# CS_NAV_SNS.net
KiCad netlist of a schematic drawn in EAGLE
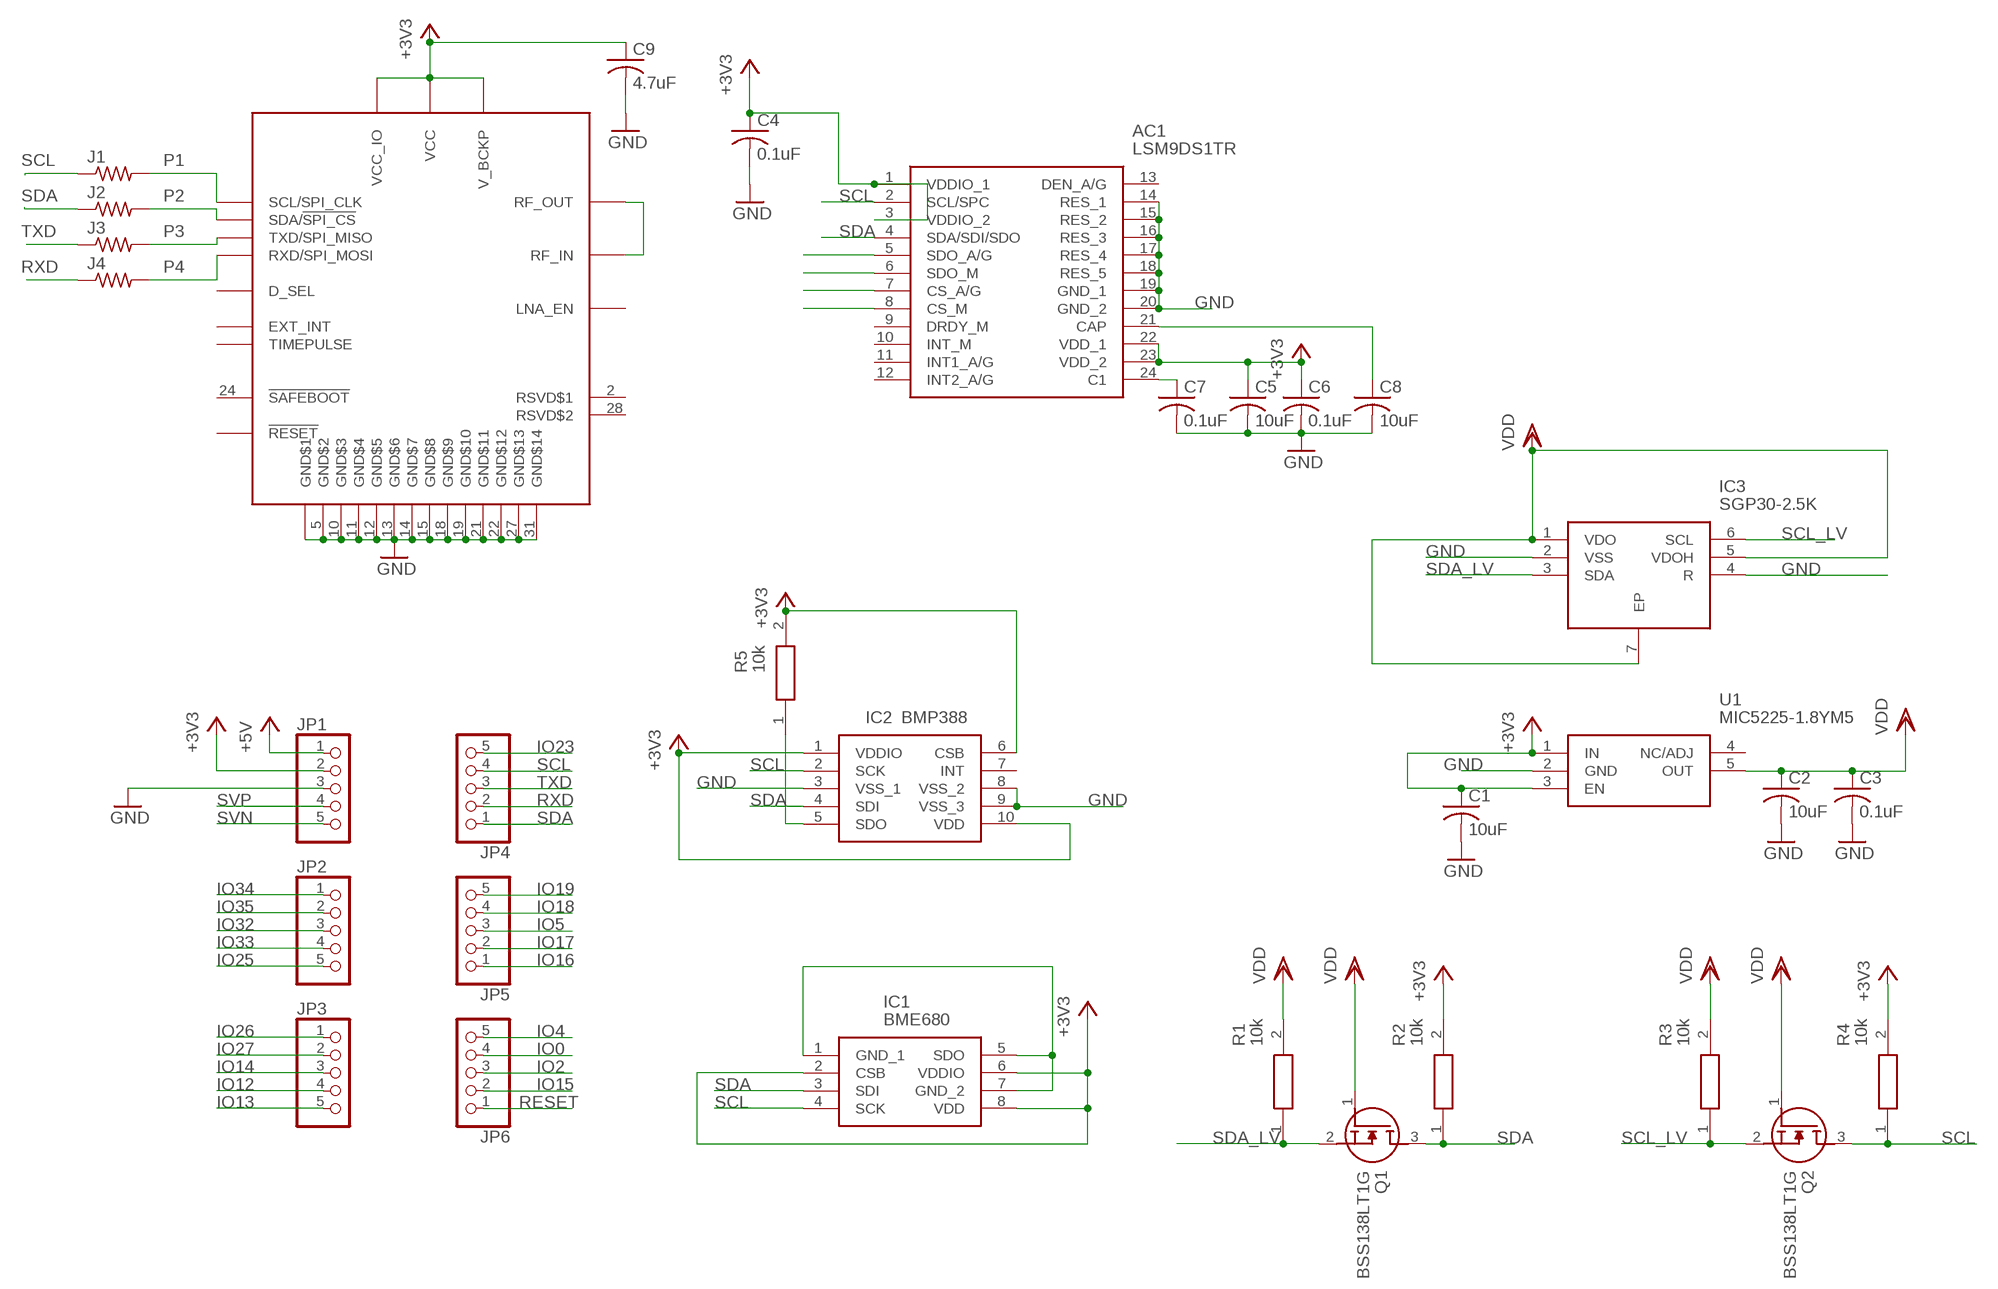
[diagram p0: schematic, sheet 1]

(export (version "E")
  (design (tool "Eeschema 10.0.6"))
  (components
    (comp (ref "AC1")
      (value "LSM9DS1TR")
      (footprint "eagle-import:LGA-24L(3X3.5X1MM)")
      (fields (field (name "MOUSER_PART_NUMBER") "511-LSM9DS1TR") (field (name "RS_PART_NUMBER") "1660908"))
      (libsource (lib "eagle-import") (part "LSM9DS1TR"))
    )
    (comp (ref "C1")
      (value "10uF")
      (footprint "eagle-import:C0805")
      (libsource (lib "eagle-import") (part "C-USC0805"))
    )
    (comp (ref "C2")
      (value "10uF")
      (footprint "eagle-import:C0805")
      (libsource (lib "eagle-import") (part "C-USC0805"))
    )
    (comp (ref "C3")
      (value "0.1uF")
      (footprint "eagle-import:C0805")
      (libsource (lib "eagle-import") (part "C-USC0805"))
    )
    (comp (ref "C4")
      (value "0.1uF")
      (footprint "eagle-import:C0805")
      (libsource (lib "eagle-import") (part "C-USC0805"))
    )
    (comp (ref "C5")
      (value "10uF")
      (footprint "eagle-import:C0805")
      (libsource (lib "eagle-import") (part "C-USC0805"))
    )
    (comp (ref "C6")
      (value "0.1uF")
      (footprint "eagle-import:C0805")
      (libsource (lib "eagle-import") (part "C-USC0805"))
    )
    (comp (ref "C7")
      (value "0.1uF")
      (footprint "eagle-import:C0805")
      (libsource (lib "eagle-import") (part "C-USC0805"))
    )
    (comp (ref "C8")
      (value "10uF")
      (footprint "eagle-import:C0805")
      (libsource (lib "eagle-import") (part "C-USC0805"))
    )
    (comp (ref "C9")
      (value "4.7uF")
      (footprint "eagle-import:C0805")
      (libsource (lib "eagle-import") (part "C-USC0805"))
    )
    (comp (ref "IC1")
      (value "BME680")
      (footprint "eagle-import:BME680")
      (fields (field (name "MOUSER_PART_NUMBER") "262-BME680"))
      (libsource (lib "eagle-import") (part "BME680"))
    )
    (comp (ref "IC2")
      (value "BMP388")
      (footprint "eagle-import:BMP388")
      (fields (field (name "MOUSER_PART_NUMBER") "262-BMP388"))
      (libsource (lib "eagle-import") (part "BMP388"))
    )
    (comp (ref "IC3")
      (value "SGP30-2.5K")
      (footprint "eagle-import:SON80P245X245X90-7N")
      (fields
        (field (name "MANUFACTURER_PART_NUMBER") "SGP30-2.5k")
        (field (name "MOUSER_PART_NUMBER") "403-SGP30-2.5K")
        (field (name "RS_PART_NUMBER") "1463573")
      )
      (libsource (lib "eagle-import") (part "SGP30-2.5K"))
    )
    (comp (ref "J1")
      (value "R-US_R1206")
      (footprint "eagle-import:R1206")
      (libsource (lib "eagle-import") (part "R-US_R1206"))
    )
    (comp (ref "J2")
      (value "R-US_R1206")
      (footprint "eagle-import:R1206")
      (libsource (lib "eagle-import") (part "R-US_R1206"))
    )
    (comp (ref "J3")
      (value "R-US_R1206")
      (footprint "eagle-import:R1206")
      (libsource (lib "eagle-import") (part "R-US_R1206"))
    )
    (comp (ref "J4")
      (value "R-US_R1206")
      (footprint "eagle-import:R1206")
      (libsource (lib "eagle-import") (part "R-US_R1206"))
    )
    (comp (ref "JP1")
      (value "PINHD-1X5")
      (footprint "eagle-import:1X05")
      (libsource (lib "eagle-import") (part "PINHD-1X5"))
    )
    (comp (ref "JP2")
      (value "PINHD-1X5")
      (footprint "eagle-import:1X05")
      (libsource (lib "eagle-import") (part "PINHD-1X5"))
    )
    (comp (ref "JP3")
      (value "PINHD-1X5")
      (footprint "eagle-import:1X05")
      (libsource (lib "eagle-import") (part "PINHD-1X5"))
    )
    (comp (ref "JP4")
      (value "PINHD-1X5")
      (footprint "eagle-import:1X05")
      (libsource (lib "eagle-import") (part "PINHD-1X5"))
    )
    (comp (ref "JP5")
      (value "PINHD-1X5")
      (footprint "eagle-import:1X05")
      (libsource (lib "eagle-import") (part "PINHD-1X5"))
    )
    (comp (ref "JP6")
      (value "PINHD-1X5")
      (footprint "eagle-import:1X05")
      (libsource (lib "eagle-import") (part "PINHD-1X5"))
    )
    (comp (ref "Q1")
      (value "BSS138LT1G")
      (footprint "eagle-import:SOT96P237X111-3N")
      (fields (field (name "MOUSER_PART_NUMBER") "863-BSS138LT1G") (field (name "RS_PART_NUMBER") "5452529P"))
      (libsource (lib "eagle-import") (part "BSS138LT1G"))
    )
    (comp (ref "Q2")
      (value "BSS138LT1G")
      (footprint "eagle-import:SOT96P237X111-3N")
      (fields (field (name "MOUSER_PART_NUMBER") "863-BSS138LT1G") (field (name "RS_PART_NUMBER") "5452529P"))
      (libsource (lib "eagle-import") (part "BSS138LT1G"))
    )
    (comp (ref "R1")
      (value "10k")
      (footprint "eagle-import:RESC2012X60N")
      (fields
        (field (name "MANUFACTURER_PART_NUMBER") "ERA-6AED134V")
        (field (name "MOUSER_PART_NUMBER") "667-ERA-6AED134V")
      )
      (libsource (lib "eagle-import") (part "ERA-6AED134V"))
    )
    (comp (ref "R2")
      (value "10k")
      (footprint "eagle-import:RESC2012X60N")
      (fields
        (field (name "MANUFACTURER_PART_NUMBER") "ERA-6AED134V")
        (field (name "MOUSER_PART_NUMBER") "667-ERA-6AED134V")
      )
      (libsource (lib "eagle-import") (part "ERA-6AED134V"))
    )
    (comp (ref "R3")
      (value "10k")
      (footprint "eagle-import:RESC2012X60N")
      (fields
        (field (name "MANUFACTURER_PART_NUMBER") "ERA-6AED134V")
        (field (name "MOUSER_PART_NUMBER") "667-ERA-6AED134V")
      )
      (libsource (lib "eagle-import") (part "ERA-6AED134V"))
    )
    (comp (ref "R4")
      (value "10k")
      (footprint "eagle-import:RESC2012X60N")
      (fields
        (field (name "MANUFACTURER_PART_NUMBER") "ERA-6AED134V")
        (field (name "MOUSER_PART_NUMBER") "667-ERA-6AED134V")
      )
      (libsource (lib "eagle-import") (part "ERA-6AED134V"))
    )
    (comp (ref "R5")
      (value "10k")
      (footprint "eagle-import:RESC2012X60N")
      (fields
        (field (name "MANUFACTURER_PART_NUMBER") "ERA-6AED134V")
        (field (name "MOUSER_PART_NUMBER") "667-ERA-6AED134V")
      )
      (libsource (lib "eagle-import") (part "ERA-6AED134V"))
    )
    (comp (ref "U$1")
      (value "CAM-M8")
      (footprint "eagle-import:CAM-M8")
      (libsource (lib "eagle-import") (part "CAM-M8"))
    )
    (comp (ref "U1")
      (value "MIC5225-1.8YM5")
      (footprint "eagle-import:SOT95P280X145-5N")
      (libsource (lib "eagle-import") (part "MIC5225-1.8YM5"))
    )
  )
  (nets
    (net (code "1") (name "+3V3") (class "Default")
      (node (ref "AC1") (pin "1") (pinfunction "VDDIO_1_1") (pintype "power_in"))
      (node (ref "AC1") (pin "22") (pinfunction "VDD_1_22") (pintype "power_in"))
      (node (ref "AC1") (pin "23") (pinfunction "VDD_2_23") (pintype "power_in"))
      (node (ref "AC1") (pin "3") (pinfunction "VDDIO_2_3") (pintype "power_in"))
      (node (ref "C1") (pin "1") (pinfunction "1_1") (pintype "passive"))
      (node (ref "C4") (pin "1") (pinfunction "1_1") (pintype "passive"))
      (node (ref "C5") (pin "1") (pinfunction "1_1") (pintype "passive"))
      (node (ref "C6") (pin "1") (pinfunction "1_1") (pintype "passive"))
      (node (ref "C9") (pin "1") (pinfunction "1_1") (pintype "passive"))
      (node (ref "IC1") (pin "2") (pinfunction "CSB_2") (pintype "bidirectional"))
      (node (ref "IC1") (pin "6") (pinfunction "VDDIO_6") (pintype "bidirectional"))
      (node (ref "IC1") (pin "8") (pinfunction "VDD_8") (pintype "bidirectional"))
      (node (ref "IC2") (pin "1") (pinfunction "VDDIO_1") (pintype "bidirectional"))
      (node (ref "IC2") (pin "10") (pinfunction "VDD_10") (pintype "bidirectional"))
      (node (ref "IC2") (pin "6") (pinfunction "CSB_6") (pintype "bidirectional"))
      (node (ref "JP1") (pin "2") (pinfunction "2_2") (pintype "passive"))
      (node (ref "R2") (pin "2") (pinfunction "2_2") (pintype "bidirectional"))
      (node (ref "R4") (pin "2") (pinfunction "2_2") (pintype "bidirectional"))
      (node (ref "R5") (pin "2") (pinfunction "2_2") (pintype "bidirectional"))
      (node (ref "U$1") (pin "1") (pinfunction "VCC_IO_1") (pintype "power_in"))
      (node (ref "U$1") (pin "8") (pinfunction "V_BCKP_8") (pintype "power_in"))
      (node (ref "U$1") (pin "9") (pinfunction "VCC_9") (pintype "power_in"))
      (node (ref "U1") (pin "1") (pinfunction "IN_1") (pintype "bidirectional"))
      (node (ref "U1") (pin "3") (pinfunction "EN_3") (pintype "bidirectional"))
    )
    (net (code "2") (name "+5V") (class "Default")
      (node (ref "JP1") (pin "1") (pinfunction "1_1") (pintype "passive"))
    )
    (net (code "3") (name "/IO0") (class "Default")
      (node (ref "JP6") (pin "4") (pinfunction "4_4") (pintype "passive"))
    )
    (net (code "4") (name "/IO2") (class "Default")
      (node (ref "JP6") (pin "3") (pinfunction "3_3") (pintype "passive"))
    )
    (net (code "5") (name "/IO4") (class "Default")
      (node (ref "JP6") (pin "5") (pinfunction "5_5") (pintype "passive"))
    )
    (net (code "6") (name "/IO5") (class "Default")
      (node (ref "JP5") (pin "3") (pinfunction "3_3") (pintype "passive"))
    )
    (net (code "7") (name "/IO12") (class "Default")
      (node (ref "JP3") (pin "4") (pinfunction "4_4") (pintype "passive"))
    )
    (net (code "8") (name "/IO13") (class "Default")
      (node (ref "JP3") (pin "5") (pinfunction "5_5") (pintype "passive"))
    )
    (net (code "9") (name "/IO14") (class "Default")
      (node (ref "JP3") (pin "3") (pinfunction "3_3") (pintype "passive"))
    )
    (net (code "10") (name "/IO15") (class "Default")
      (node (ref "JP6") (pin "2") (pinfunction "2_2") (pintype "passive"))
    )
    (net (code "11") (name "/IO16") (class "Default")
      (node (ref "JP5") (pin "1") (pinfunction "1_1") (pintype "passive"))
    )
    (net (code "12") (name "/IO17") (class "Default")
      (node (ref "JP5") (pin "2") (pinfunction "2_2") (pintype "passive"))
    )
    (net (code "13") (name "/IO18") (class "Default")
      (node (ref "JP5") (pin "4") (pinfunction "4_4") (pintype "passive"))
    )
    (net (code "14") (name "/IO19") (class "Default")
      (node (ref "JP5") (pin "5") (pinfunction "5_5") (pintype "passive"))
    )
    (net (code "15") (name "/IO23") (class "Default")
      (node (ref "JP4") (pin "5") (pinfunction "5_5") (pintype "passive"))
    )
    (net (code "16") (name "/IO25") (class "Default")
      (node (ref "JP2") (pin "5") (pinfunction "5_5") (pintype "passive"))
    )
    (net (code "17") (name "/IO26") (class "Default")
      (node (ref "JP3") (pin "1") (pinfunction "1_1") (pintype "passive"))
    )
    (net (code "18") (name "/IO27") (class "Default")
      (node (ref "JP3") (pin "2") (pinfunction "2_2") (pintype "passive"))
    )
    (net (code "19") (name "/IO32") (class "Default")
      (node (ref "JP2") (pin "3") (pinfunction "3_3") (pintype "passive"))
    )
    (net (code "20") (name "/IO33") (class "Default")
      (node (ref "JP2") (pin "4") (pinfunction "4_4") (pintype "passive"))
    )
    (net (code "21") (name "/IO34") (class "Default")
      (node (ref "JP2") (pin "1") (pinfunction "1_1") (pintype "passive"))
    )
    (net (code "22") (name "/IO35") (class "Default")
      (node (ref "JP2") (pin "2") (pinfunction "2_2") (pintype "passive"))
    )
    (net (code "23") (name "/P1") (class "Default")
      (node (ref "J1") (pin "2") (pinfunction "2_2") (pintype "passive"))
      (node (ref "U$1") (pin "6") (pinfunction "SCL/SPI_CLK_6") (pintype "input"))
    )
    (net (code "24") (name "/P2") (class "Default")
      (node (ref "J2") (pin "2") (pinfunction "2_2") (pintype "passive"))
      (node (ref "U$1") (pin "3") (pinfunction "SDA/~{SPI_CS}_3") (pintype "bidirectional"))
    )
    (net (code "25") (name "/P3") (class "Default")
      (node (ref "J3") (pin "2") (pinfunction "2_2") (pintype "passive"))
      (node (ref "U$1") (pin "25") (pinfunction "TXD/SPI_MISO_25") (pintype "output"))
    )
    (net (code "26") (name "/P4") (class "Default")
      (node (ref "J4") (pin "2") (pinfunction "2_2") (pintype "passive"))
      (node (ref "U$1") (pin "26") (pinfunction "RXD/SPI_MOSI_26") (pintype "input"))
    )
    (net (code "27") (name "/RESET") (class "Default")
      (node (ref "JP6") (pin "1") (pinfunction "1_1") (pintype "passive"))
    )
    (net (code "28") (name "/RXD") (class "Default")
      (node (ref "J4") (pin "1") (pinfunction "1_1") (pintype "passive"))
      (node (ref "JP4") (pin "2") (pinfunction "2_2") (pintype "passive"))
    )
    (net (code "29") (name "/SCL") (class "Default")
      (node (ref "AC1") (pin "2") (pinfunction "SCL/SPC_2") (pintype "output"))
      (node (ref "IC1") (pin "4") (pinfunction "SCK_4") (pintype "bidirectional"))
      (node (ref "IC2") (pin "2") (pinfunction "SCK_2") (pintype "bidirectional"))
      (node (ref "J1") (pin "1") (pinfunction "1_1") (pintype "passive"))
      (node (ref "JP4") (pin "4") (pinfunction "4_4") (pintype "passive"))
      (node (ref "Q2") (pin "3") (pinfunction "D_3") (pintype "bidirectional"))
      (node (ref "R4") (pin "1") (pinfunction "1_1") (pintype "bidirectional"))
    )
    (net (code "30") (name "/SCL_LV") (class "Default")
      (node (ref "IC3") (pin "6") (pinfunction "SCL_6") (pintype "bidirectional"))
      (node (ref "Q2") (pin "2") (pinfunction "S_2") (pintype "bidirectional"))
      (node (ref "R3") (pin "1") (pinfunction "1_1") (pintype "bidirectional"))
    )
    (net (code "31") (name "/SDA") (class "Default")
      (node (ref "AC1") (pin "4") (pinfunction "SDA/SDI/SDO_4") (pintype "bidirectional"))
      (node (ref "IC1") (pin "3") (pinfunction "SDI_3") (pintype "bidirectional"))
      (node (ref "IC2") (pin "4") (pinfunction "SDI_4") (pintype "bidirectional"))
      (node (ref "J2") (pin "1") (pinfunction "1_1") (pintype "passive"))
      (node (ref "JP4") (pin "1") (pinfunction "1_1") (pintype "passive"))
      (node (ref "Q1") (pin "3") (pinfunction "D_3") (pintype "bidirectional"))
      (node (ref "R2") (pin "1") (pinfunction "1_1") (pintype "bidirectional"))
    )
    (net (code "32") (name "/SDA_LV") (class "Default")
      (node (ref "IC3") (pin "3") (pinfunction "SDA_3") (pintype "bidirectional"))
      (node (ref "Q1") (pin "2") (pinfunction "S_2") (pintype "bidirectional"))
      (node (ref "R1") (pin "1") (pinfunction "1_1") (pintype "bidirectional"))
    )
    (net (code "33") (name "/SVN") (class "Default")
      (node (ref "JP1") (pin "5") (pinfunction "5_5") (pintype "passive"))
    )
    (net (code "34") (name "/SVP") (class "Default")
      (node (ref "JP1") (pin "4") (pinfunction "4_4") (pintype "passive"))
    )
    (net (code "35") (name "/TXD") (class "Default")
      (node (ref "J3") (pin "1") (pinfunction "1_1") (pintype "passive"))
      (node (ref "JP4") (pin "3") (pinfunction "3_3") (pintype "passive"))
    )
    (net (code "36") (name "GND") (class "Default")
      (node (ref "AC1") (pin "14") (pinfunction "RES_1_14") (pintype "power_in"))
      (node (ref "AC1") (pin "15") (pinfunction "RES_2_15") (pintype "power_in"))
      (node (ref "AC1") (pin "16") (pinfunction "RES_3_16") (pintype "power_in"))
      (node (ref "AC1") (pin "17") (pinfunction "RES_4_17") (pintype "power_in"))
      (node (ref "AC1") (pin "18") (pinfunction "RES_5_18") (pintype "power_in"))
      (node (ref "AC1") (pin "19") (pinfunction "GND_1_19") (pintype "power_in"))
      (node (ref "AC1") (pin "20") (pinfunction "GND_2_20") (pintype "power_in"))
      (node (ref "C1") (pin "2") (pinfunction "2_2") (pintype "passive"))
      (node (ref "C2") (pin "2") (pinfunction "2_2") (pintype "passive"))
      (node (ref "C3") (pin "2") (pinfunction "2_2") (pintype "passive"))
      (node (ref "C4") (pin "2") (pinfunction "2_2") (pintype "passive"))
      (node (ref "C5") (pin "2") (pinfunction "2_2") (pintype "passive"))
      (node (ref "C6") (pin "2") (pinfunction "2_2") (pintype "passive"))
      (node (ref "C7") (pin "2") (pinfunction "2_2") (pintype "passive"))
      (node (ref "C8") (pin "2") (pinfunction "2_2") (pintype "passive"))
      (node (ref "C9") (pin "2") (pinfunction "2_2") (pintype "passive"))
      (node (ref "IC2") (pin "3") (pinfunction "VSS_1_3") (pintype "bidirectional"))
      (node (ref "IC2") (pin "8") (pinfunction "VSS_2_8") (pintype "bidirectional"))
      (node (ref "IC2") (pin "9") (pinfunction "VSS_3_9") (pintype "bidirectional"))
      (node (ref "IC3") (pin "2") (pinfunction "VSS_2") (pintype "power_in"))
      (node (ref "IC3") (pin "4") (pinfunction "R_4") (pintype "power_in"))
      (node (ref "JP1") (pin "3") (pinfunction "3_3") (pintype "passive"))
      (node (ref "U$1") (pin "10") (pinfunction "GND$3_10") (pintype "power_in"))
      (node (ref "U$1") (pin "11") (pinfunction "GND$4_11") (pintype "power_in"))
      (node (ref "U$1") (pin "12") (pinfunction "GND$5_12") (pintype "power_in"))
      (node (ref "U$1") (pin "13") (pinfunction "GND$6_13") (pintype "power_in"))
      (node (ref "U$1") (pin "14") (pinfunction "GND$7_14") (pintype "power_in"))
      (node (ref "U$1") (pin "15") (pinfunction "GND$8_15") (pintype "power_in"))
      (node (ref "U$1") (pin "18") (pinfunction "GND$9_18") (pintype "power_in"))
      (node (ref "U$1") (pin "19") (pinfunction "GND$10_19") (pintype "power_in"))
      (node (ref "U$1") (pin "21") (pinfunction "GND$11_21") (pintype "power_in"))
      (node (ref "U$1") (pin "22") (pinfunction "GND$12_22") (pintype "power_in"))
      (node (ref "U$1") (pin "27") (pinfunction "GND$13_27") (pintype "power_in"))
      (node (ref "U$1") (pin "31") (pinfunction "GND$14_31") (pintype "power_in"))
      (node (ref "U$1") (pin "4") (pinfunction "GND$1_4") (pintype "power_in"))
      (node (ref "U$1") (pin "5") (pinfunction "GND$2_5") (pintype "power_in"))
      (node (ref "U1") (pin "2") (pinfunction "GND_2") (pintype "bidirectional"))
    )
    (net (code "37") (name "Net-(AC1-C1)") (class "Default")
      (node (ref "AC1") (pin "24") (pinfunction "C1_24") (pintype "bidirectional"))
      (node (ref "C7") (pin "1") (pinfunction "1_1") (pintype "passive"))
    )
    (net (code "38") (name "Net-(AC1-CAP)") (class "Default")
      (node (ref "AC1") (pin "21") (pinfunction "CAP_21") (pintype "power_in"))
      (node (ref "C8") (pin "1") (pinfunction "1_1") (pintype "passive"))
    )
    (net (code "39") (name "Net-(IC1-GND_1)") (class "Default")
      (node (ref "IC1") (pin "1") (pinfunction "GND_1_1") (pintype "bidirectional"))
      (node (ref "IC1") (pin "5") (pinfunction "SDO_5") (pintype "bidirectional"))
      (node (ref "IC1") (pin "7") (pinfunction "GND_2_7") (pintype "bidirectional"))
    )
    (net (code "40") (name "Net-(IC2-SDO)") (class "Default")
      (node (ref "IC2") (pin "5") (pinfunction "SDO_5") (pintype "bidirectional"))
      (node (ref "R5") (pin "1") (pinfunction "1_1") (pintype "bidirectional"))
    )
    (net (code "41") (name "Net-(U$1-RF_IN)") (class "Default")
      (node (ref "U$1") (pin "16") (pinfunction "RF_OUT_16") (pintype "output"))
      (node (ref "U$1") (pin "17") (pinfunction "RF_IN_17") (pintype "input"))
    )
    (net (code "42") (name "VDD") (class "Default")
      (node (ref "C2") (pin "1") (pinfunction "1_1") (pintype "passive"))
      (node (ref "C3") (pin "1") (pinfunction "1_1") (pintype "passive"))
      (node (ref "IC3") (pin "1") (pinfunction "VDO_1") (pintype "power_in"))
      (node (ref "IC3") (pin "5") (pinfunction "VDOH_5") (pintype "power_in"))
      (node (ref "IC3") (pin "7") (pinfunction "EP_7") (pintype "bidirectional"))
      (node (ref "Q1") (pin "1") (pinfunction "G_1") (pintype "bidirectional"))
      (node (ref "Q2") (pin "1") (pinfunction "G_1") (pintype "bidirectional"))
      (node (ref "R1") (pin "2") (pinfunction "2_2") (pintype "bidirectional"))
      (node (ref "R3") (pin "2") (pinfunction "2_2") (pintype "bidirectional"))
      (node (ref "U1") (pin "5") (pinfunction "OUT_5") (pintype "bidirectional"))
    )
    (net (code "43") (name "unconnected-(AC1-CS_A{slash}G-Pad7)") (class "Default")
      (node (ref "AC1") (pin "7") (pinfunction "CS_A/G_7") (pintype "bidirectional"))
    )
    (net (code "44") (name "unconnected-(AC1-CS_M-Pad8)") (class "Default")
      (node (ref "AC1") (pin "8") (pinfunction "CS_M_8") (pintype "bidirectional"))
    )
    (net (code "45") (name "unconnected-(AC1-DEN_A{slash}G-Pad13)") (class "Default")
      (node (ref "AC1") (pin "13") (pinfunction "DEN_A/G_13") (pintype "bidirectional"))
    )
    (net (code "46") (name "unconnected-(AC1-DRDY_M-Pad9)") (class "Default")
      (node (ref "AC1") (pin "9") (pinfunction "DRDY_M_9") (pintype "bidirectional"))
    )
    (net (code "47") (name "unconnected-(AC1-INT1_A{slash}G-Pad11)") (class "Default")
      (node (ref "AC1") (pin "11") (pinfunction "INT1_A/G_11") (pintype "bidirectional"))
    )
    (net (code "48") (name "unconnected-(AC1-INT2_A{slash}G-Pad12)") (class "Default")
      (node (ref "AC1") (pin "12") (pinfunction "INT2_A/G_12") (pintype "bidirectional"))
    )
    (net (code "49") (name "unconnected-(AC1-INT_M-Pad10)") (class "Default")
      (node (ref "AC1") (pin "10") (pinfunction "INT_M_10") (pintype "bidirectional"))
    )
    (net (code "50") (name "unconnected-(AC1-SDO_A{slash}G-Pad5)") (class "Default")
      (node (ref "AC1") (pin "5") (pinfunction "SDO_A/G_5") (pintype "output"))
    )
    (net (code "51") (name "unconnected-(AC1-SDO_M-Pad6)") (class "Default")
      (node (ref "AC1") (pin "6") (pinfunction "SDO_M_6") (pintype "output"))
    )
    (net (code "52") (name "unconnected-(IC2-INT-Pad7)") (class "Default")
      (node (ref "IC2") (pin "7") (pinfunction "INT_7") (pintype "bidirectional"))
    )
    (net (code "53") (name "unconnected-(U$1-D_SEL-Pad20)") (class "Default")
      (node (ref "U$1") (pin "20") (pinfunction "D_SEL_20") (pintype "input"))
    )
    (net (code "54") (name "unconnected-(U$1-EXT_INT-Pad7)") (class "Default")
      (node (ref "U$1") (pin "7") (pinfunction "EXT_INT_7") (pintype "bidirectional"))
    )
    (net (code "55") (name "unconnected-(U$1-LNA_EN-Pad30)") (class "Default")
      (node (ref "U$1") (pin "30") (pinfunction "LNA_EN_30") (pintype "output"))
    )
    (net (code "56") (name "unconnected-(U$1-RSVD$1-Pad2)") (class "Default")
      (node (ref "U$1") (pin "2") (pinfunction "RSVD$1_2") (pintype "no_connect"))
    )
    (net (code "57") (name "unconnected-(U$1-RSVD$2-Pad28)") (class "Default")
      (node (ref "U$1") (pin "28") (pinfunction "RSVD$2_28") (pintype "no_connect"))
    )
    (net (code "58") (name "unconnected-(U$1-TIMEPULSE-Pad29)") (class "Default")
      (node (ref "U$1") (pin "29") (pinfunction "TIMEPULSE_29") (pintype "output"))
    )
    (net (code "59") (name "unconnected-(U$1-~{RESET}-Pad23)") (class "Default")
      (node (ref "U$1") (pin "23") (pinfunction "~{RESET}_23") (pintype "input"))
    )
    (net (code "60") (name "unconnected-(U$1-~{SAFEBOOT}-Pad24)") (class "Default")
      (node (ref "U$1") (pin "24") (pinfunction "~{SAFEBOOT}_24") (pintype "input"))
    )
    (net (code "61") (name "unconnected-(U1-NC{slash}ADJ-Pad4)") (class "Default")
      (node (ref "U1") (pin "4") (pinfunction "NC/ADJ_4") (pintype "bidirectional"))
    )
  )
)
